# Connect.net
KiCad netlist of a schematic drawn in Altium Designer
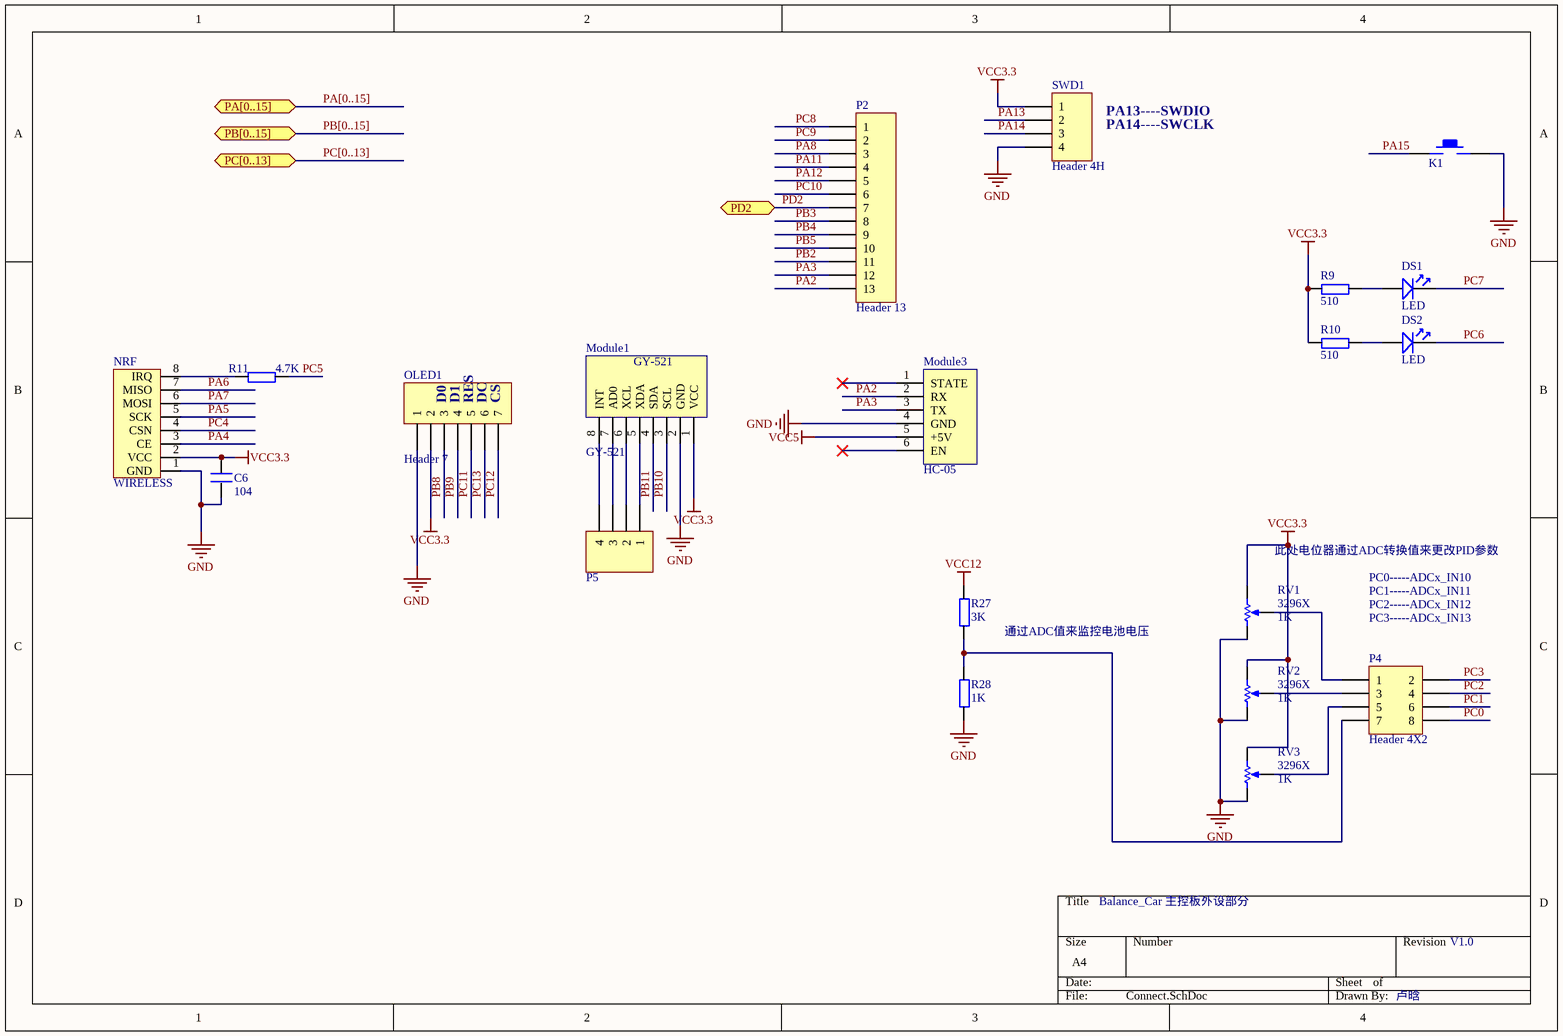
[diagram p0: Connect.SchDoc]

(export (version "E")
  (design (tool "Eeschema 10.0.6"))
  (components
    (comp (ref "C6") (value "104") (footprint "0603C") (libsource (lib "WarShip V3 STM32103封装库") (part "C")))
    (comp (ref "DS1") (value "LED") (footprint "0603D-R") (libsource (lib "STM32F429核心板封装库") (part "LED")))
    (comp (ref "DS2") (value "LED") (footprint "0603D-R") (libsource (lib "STM32F429核心板封装库") (part "LED")))
    (comp (ref "K1")
      (value "KEY_M")
      (footprint "KEY_SOP3625_B")
      (libsource (lib "STM32F429核心板封装库") (part "KEY_M"))
    )
    (comp (ref "Module1") (value "GY-521") (footprint "GY-521") (libsource (lib "3D库") (part "GY-521")))
    (comp (ref "Module3")
      (value "HC-05")
      (footprint "HC-05")
      (description "Bluetooth Module(HC-05)")
      (libsource (lib "Modules-3D") (part "HC-05"))
    )
    (comp (ref "NRF") (value "WIRELESS") (footprint "NRF24L01") (libsource (lib "3D库") (part "NRF24L01")))
    (comp (ref "OLED1")
      (value "Header 7")
      (footprint "HDR1X7")
      (description "Header, 7-Pin")
      (fields (field (name "PUBLISHER") "Altium Limited"))
      (libsource (lib "Miscellaneous Connectors") (part "Header 7"))
    )
    (comp (ref "P2")
      (value "Header 13")
      (footprint "HDR1X13")
      (description "Header, 13-Pin")
      (fields (field (name "PUBLISHER") "Altium Limited"))
      (libsource (lib "Miscellaneous Connectors") (part "Header 13"))
    )
    (comp (ref "P4")
      (value "Header 4X2")
      (footprint "HDR2X4")
      (description "Header, 4-Pin, Dual row")
      (fields (field (name "PUBLISHER") "Altium Limited"))
      (libsource (lib "Miscellaneous Connectors") (part "Header 4X2"))
    )
    (comp (ref "P5")
      (value "Header 4")
      (footprint "HDR_1x4_2R54_V_M")
      (description "Header, 4-Pin, Single row")
      (fields (field (name "PUBLISHER") "Altium Limited"))
      (libsource (lib "3D库") (part "Header 4"))
    )
    (comp (ref "R9") (value "510") (footprint "0603R") (libsource (lib "Explorer STM32F407封装库") (part "R")))
    (comp (ref "R10") (value "510") (footprint "0603R") (libsource (lib "Explorer STM32F407封装库") (part "R")))
    (comp (ref "R11") (value "4.7K") (footprint "0603R") (libsource (lib "Explorer STM32F407封装库") (part "R")))
    (comp (ref "R27") (value "3K") (footprint "0603R") (libsource (lib "STM32F429核心板封装库") (part "R")))
    (comp (ref "R28") (value "1K") (footprint "0603R") (libsource (lib "STM32F429核心板封装库") (part "R")))
    (comp (ref "RV1")
      (value "3296X")
      (footprint "VR5-R")
      (description "Potentiometer")
      (fields (field (name "ALTIUM_VALUE") "1K") (field (name "PUBLISHER") "Altium Limited"))
      (libsource (lib "3D库") (part "RPot"))
    )
    (comp (ref "RV2")
      (value "3296X")
      (footprint "VR5-R")
      (description "Potentiometer")
      (fields (field (name "ALTIUM_VALUE") "1K") (field (name "PUBLISHER") "Altium Limited"))
      (libsource (lib "3D库") (part "RPot"))
    )
    (comp (ref "RV3")
      (value "3296X")
      (footprint "VR5-R")
      (description "Potentiometer")
      (fields (field (name "ALTIUM_VALUE") "1K") (field (name "PUBLISHER") "Altium Limited"))
      (libsource (lib "3D库") (part "RPot"))
    )
    (comp (ref "SWD1")
      (value "Header 4H")
      (footprint "HDR1X4H")
      (description "Header, 4-Pin, Right Angle")
      (fields (field (name "PUBLISHER") "Altium Limited"))
      (libsource (lib "Miscellaneous Connectors") (part "Header 4H"))
    )
  )
  (nets
    (net (code "13") (name "/PA2") (class "Default")
      (node (ref "Module3") (pin "2") (pinfunction "RX_2") (pintype "passive"))
      (node (ref "P2") (pin "13") (pinfunction "13_13") (pintype "passive"))
    )
    (net (code "14") (name "/PA3") (class "Default")
      (node (ref "Module3") (pin "3") (pinfunction "TX_3") (pintype "passive"))
      (node (ref "P2") (pin "12") (pinfunction "12_12") (pintype "passive"))
    )
    (net (code "15") (name "/PA4") (class "Default")
      (node (ref "NRF") (pin "3") (pinfunction "CE_3") (pintype "passive"))
    )
    (net (code "16") (name "/PA5") (class "Default")
      (node (ref "NRF") (pin "5") (pinfunction "SCK_5") (pintype "passive"))
    )
    (net (code "17") (name "/PA6") (class "Default")
      (node (ref "NRF") (pin "7") (pinfunction "MISO_7") (pintype "passive"))
    )
    (net (code "18") (name "/PA7") (class "Default")
      (node (ref "NRF") (pin "6") (pinfunction "MOSI_6") (pintype "passive"))
    )
    (net (code "19") (name "/PA8") (class "Default")
      (node (ref "P2") (pin "3") (pinfunction "3_3") (pintype "passive"))
    )
    (net (code "20") (name "/PA11") (class "Default")
      (node (ref "P2") (pin "4") (pinfunction "4_4") (pintype "passive"))
    )
    (net (code "21") (name "/PA12") (class "Default")
      (node (ref "P2") (pin "5") (pinfunction "5_5") (pintype "passive"))
    )
    (net (code "22") (name "/PA13") (class "Default")
      (node (ref "SWD1") (pin "2") (pinfunction "2_2") (pintype "passive"))
    )
    (net (code "23") (name "/PA14") (class "Default")
      (node (ref "SWD1") (pin "3") (pinfunction "3_3") (pintype "passive"))
    )
    (net (code "24") (name "/PA15") (class "Default")
      (node (ref "K1") (pin "1") (pinfunction "1_1") (pintype "passive"))
    )
    (net (code "26") (name "/PB2") (class "Default")
      (node (ref "P2") (pin "11") (pinfunction "11_11") (pintype "passive"))
    )
    (net (code "27") (name "/PB3") (class "Default")
      (node (ref "P2") (pin "8") (pinfunction "8_8") (pintype "passive"))
    )
    (net (code "28") (name "/PB4") (class "Default")
      (node (ref "P2") (pin "9") (pinfunction "9_9") (pintype "passive"))
    )
    (net (code "29") (name "/PB5") (class "Default")
      (node (ref "P2") (pin "10") (pinfunction "10_10") (pintype "passive"))
    )
    (net (code "30") (name "/PB8") (class "Default")
      (node (ref "OLED1") (pin "3") (pinfunction "3_3") (pintype "passive"))
    )
    (net (code "31") (name "/PB9") (class "Default")
      (node (ref "OLED1") (pin "4") (pinfunction "4_4") (pintype "passive"))
    )
    (net (code "32") (name "/PB10") (class "Default")
      (node (ref "Module1") (pin "3") (pinfunction "SCL_3") (pintype "passive"))
    )
    (net (code "33") (name "/PB11") (class "Default")
      (node (ref "Module1") (pin "4") (pinfunction "SDA_4") (pintype "passive"))
    )
    (net (code "35") (name "/PC0") (class "Default")
      (node (ref "P4") (pin "8") (pinfunction "8_8") (pintype "passive"))
    )
    (net (code "36") (name "/PC1") (class "Default")
      (node (ref "P4") (pin "6") (pinfunction "6_6") (pintype "passive"))
    )
    (net (code "37") (name "/PC2") (class "Default")
      (node (ref "P4") (pin "4") (pinfunction "4_4") (pintype "passive"))
    )
    (net (code "38") (name "/PC3") (class "Default")
      (node (ref "P4") (pin "2") (pinfunction "2_2") (pintype "passive"))
    )
    (net (code "39") (name "/PC4") (class "Default")
      (node (ref "NRF") (pin "4") (pinfunction "CSN_4") (pintype "passive"))
    )
    (net (code "40") (name "/PC5") (class "Default") (node (ref "R11") (pin "2") (pintype "passive")))
    (net (code "41") (name "/PC6") (class "Default")
      (node (ref "DS2") (pin "2") (pinfunction "2_2") (pintype "passive"))
    )
    (net (code "42") (name "/PC7") (class "Default")
      (node (ref "DS1") (pin "2") (pinfunction "2_2") (pintype "passive"))
    )
    (net (code "43") (name "/PC8") (class "Default")
      (node (ref "P2") (pin "1") (pinfunction "1_1") (pintype "passive"))
    )
    (net (code "44") (name "/PC9") (class "Default")
      (node (ref "P2") (pin "2") (pinfunction "2_2") (pintype "passive"))
    )
    (net (code "45") (name "/PC10") (class "Default")
      (node (ref "P2") (pin "6") (pinfunction "6_6") (pintype "passive"))
    )
    (net (code "46") (name "/PC11") (class "Default")
      (node (ref "OLED1") (pin "5") (pinfunction "5_5") (pintype "passive"))
    )
    (net (code "47") (name "/PC12") (class "Default")
      (node (ref "OLED1") (pin "7") (pinfunction "7_7") (pintype "passive"))
    )
    (net (code "48") (name "/PC13") (class "Default")
      (node (ref "OLED1") (pin "6") (pinfunction "6_6") (pintype "passive"))
    )
    (net (code "50") (name "/PD2") (class "Default")
      (node (ref "P2") (pin "7") (pinfunction "7_7") (pintype "passive"))
    )
    (net (code "51") (name "GND") (class "Default")
      (node (ref "C6") (pin "1") (pintype "passive"))
      (node (ref "K1") (pin "2") (pinfunction "2_2") (pintype "passive"))
      (node (ref "Module1") (pin "2") (pinfunction "GND_2") (pintype "passive"))
      (node (ref "Module3") (pin "4") (pinfunction "GND_4") (pintype "passive"))
      (node (ref "NRF") (pin "1") (pinfunction "GND_1") (pintype "passive"))
      (node (ref "OLED1") (pin "1") (pinfunction "1_1") (pintype "passive"))
      (node (ref "R28") (pin "1") (pintype "passive"))
      (node (ref "RV1") (pin "1") (pinfunction "TOP_1") (pintype "passive"))
      (node (ref "RV2") (pin "1") (pinfunction "TOP_1") (pintype "passive"))
      (node (ref "RV3") (pin "1") (pinfunction "TOP_1") (pintype "passive"))
      (node (ref "SWD1") (pin "4") (pinfunction "4_4") (pintype "passive"))
    )
    (net (code "52") (name "Net-(DS1-Pad1)") (class "Default")
      (node (ref "DS1") (pin "1") (pinfunction "1_1") (pintype "passive"))
      (node (ref "R9") (pin "2") (pintype "passive"))
    )
    (net (code "53") (name "Net-(DS2-Pad1)") (class "Default")
      (node (ref "DS2") (pin "1") (pinfunction "1_1") (pintype "passive"))
      (node (ref "R10") (pin "2") (pintype "passive"))
    )
    (net (code "54") (name "Net-(Module1-AD0)") (class "Default")
      (node (ref "Module1") (pin "7") (pinfunction "AD0_7") (pintype "passive"))
      (node (ref "P5") (pin "3") (pinfunction "3_3") (pintype "passive"))
    )
    (net (code "55") (name "Net-(Module1-INT)") (class "Default")
      (node (ref "Module1") (pin "8") (pinfunction "INT_8") (pintype "passive"))
      (node (ref "P5") (pin "4") (pinfunction "4_4") (pintype "passive"))
    )
    (net (code "56") (name "Net-(Module1-XCL)") (class "Default")
      (node (ref "Module1") (pin "6") (pinfunction "XCL_6") (pintype "passive"))
      (node (ref "P5") (pin "2") (pinfunction "2_2") (pintype "passive"))
    )
    (net (code "57") (name "Net-(Module1-XDA)") (class "Default")
      (node (ref "Module1") (pin "5") (pinfunction "XDA_5") (pintype "passive"))
      (node (ref "P5") (pin "1") (pinfunction "1_1") (pintype "passive"))
    )
    (net (code "58") (name "Net-(NRF-IRQ)") (class "Default")
      (node (ref "NRF") (pin "8") (pinfunction "IRQ_8") (pintype "passive"))
      (node (ref "R11") (pin "1") (pintype "passive"))
    )
    (net (code "59") (name "Net-(P4-Pad7)") (class "Default")
      (node (ref "P4") (pin "7") (pinfunction "7_7") (pintype "passive"))
      (node (ref "R27") (pin "1") (pintype "passive"))
      (node (ref "R28") (pin "2") (pintype "passive"))
    )
    (net (code "60") (name "Net-(RV1-BOT)") (class "Default")
      (node (ref "P4") (pin "1") (pinfunction "1_1") (pintype "passive"))
      (node (ref "RV1") (pin "2") (pinfunction "BOT_2") (pintype "passive"))
    )
    (net (code "61") (name "Net-(RV2-BOT)") (class "Default")
      (node (ref "P4") (pin "3") (pinfunction "3_3") (pintype "passive"))
      (node (ref "RV2") (pin "2") (pinfunction "BOT_2") (pintype "passive"))
    )
    (net (code "62") (name "Net-(RV3-BOT)") (class "Default")
      (node (ref "P4") (pin "5") (pinfunction "5_5") (pintype "passive"))
      (node (ref "RV3") (pin "2") (pinfunction "BOT_2") (pintype "passive"))
    )
    (net (code "63") (name "VCC3.3") (class "Default")
      (node (ref "C6") (pin "2") (pintype "passive"))
      (node (ref "Module1") (pin "1") (pinfunction "VCC_1") (pintype "passive"))
      (node (ref "NRF") (pin "2") (pinfunction "VCC_2") (pintype "passive"))
      (node (ref "OLED1") (pin "2") (pinfunction "2_2") (pintype "passive"))
      (node (ref "R10") (pin "1") (pintype "passive"))
      (node (ref "R9") (pin "1") (pintype "passive"))
      (node (ref "RV1") (pin "3") (pinfunction "TAP_3") (pintype "passive"))
      (node (ref "RV2") (pin "3") (pinfunction "TAP_3") (pintype "passive"))
      (node (ref "RV3") (pin "3") (pinfunction "TAP_3") (pintype "passive"))
      (node (ref "SWD1") (pin "1") (pinfunction "1_1") (pintype "passive"))
    )
    (net (code "64") (name "VCC5") (class "Default")
      (node (ref "Module3") (pin "5") (pinfunction "+5V_5") (pintype "passive"))
    )
    (net (code "65") (name "VCC12") (class "Default") (node (ref "R27") (pin "2") (pintype "passive")))
    (net (code "66") (name "unconnected-(Module3-EN-Pad6)") (class "Default")
      (node (ref "Module3") (pin "6") (pinfunction "EN_6") (pintype "passive+no_connect"))
    )
    (net (code "67") (name "unconnected-(Module3-STATE-Pad1)") (class "Default")
      (node (ref "Module3") (pin "1") (pinfunction "STATE_1") (pintype "passive+no_connect"))
    )
  )
)
